# ppc_sys.net
KiCad netlist of a schematic drawn in Altium Designer
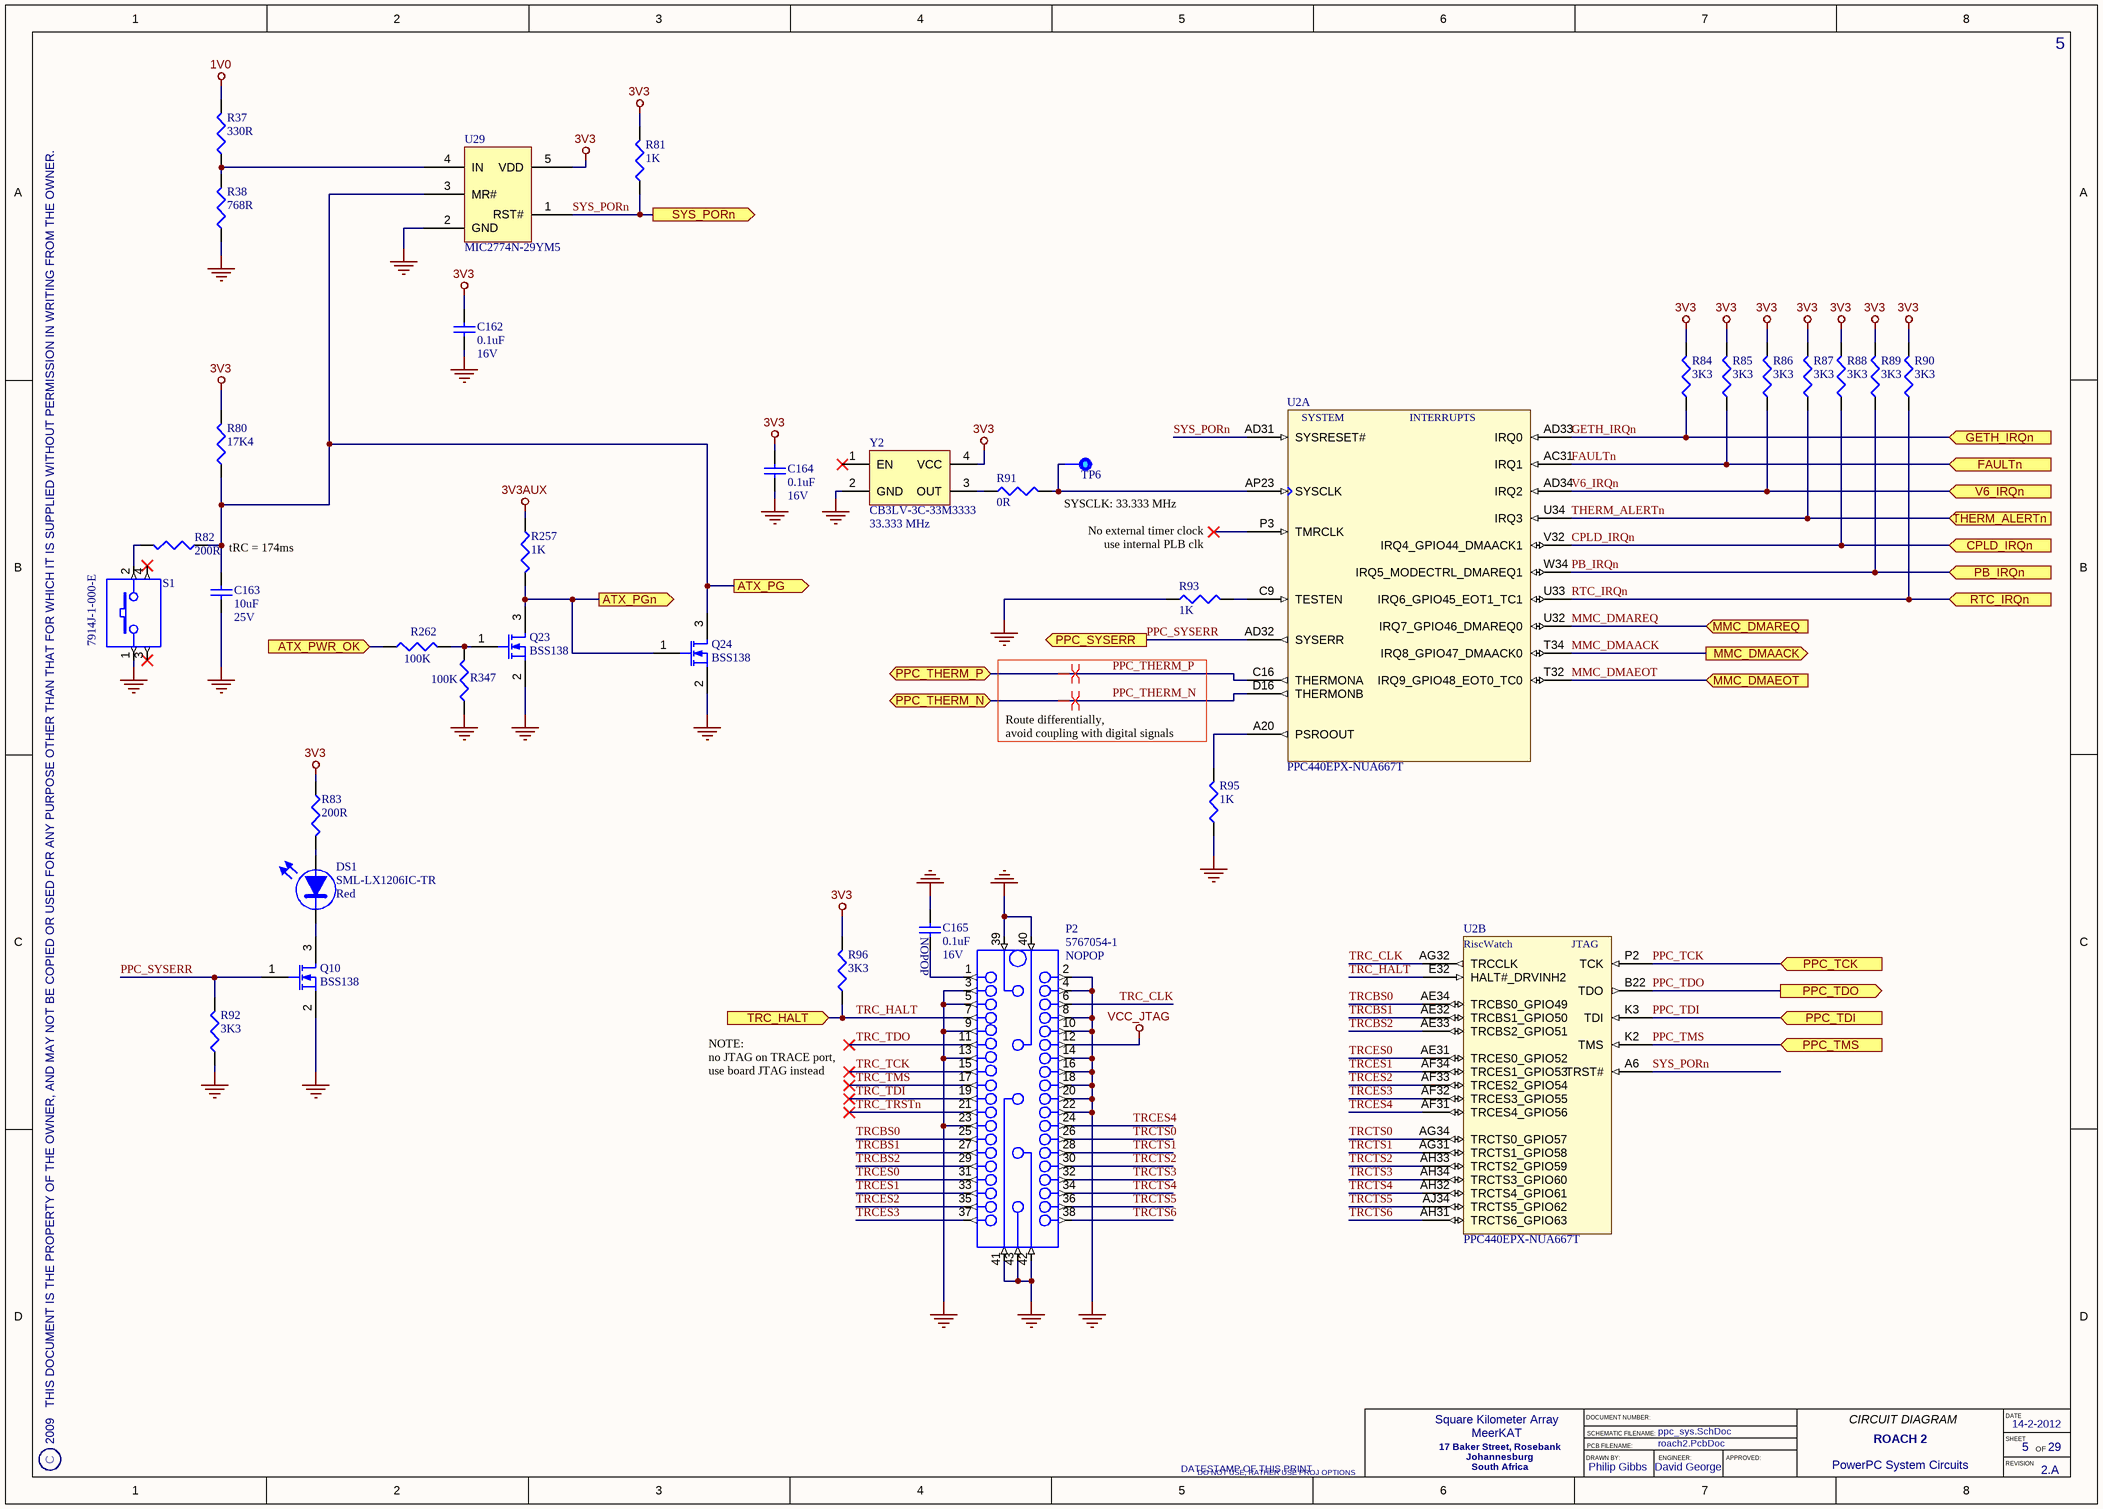
[diagram p0: ppc_sys.SchDoc]

(export (version "E")
  (design (tool "Eeschema 10.0.6"))
  (components
    (comp (ref "C162")
      (value "0.1uF")
      (footprint "CAPC1005X60L")
      (description "0.1uF, Ceramic Capacitor")
      (fields
        (field (name "RATING") "16V")
        (field (name "MANUFACTURER") "VENKEL")
        (field (name "PARTNUM") "C0402X7R160-104KN")
      )
      (libsource (lib "altium_db") (part "CapStd"))
    )
    (comp (ref "C163")
      (value "10uF")
      (footprint "CAPC3225X200L")
      (description "10uF, Ceramic Capacitor")
      (fields
        (field (name "RATING") "25V")
        (field (name "MANUFACTURER") "MURATA")
        (field (name "PARTNUM") "GRM32DR61E106KA12L")
      )
      (libsource (lib "altium_db") (part "CapStd"))
    )
    (comp (ref "C164")
      (value "0.1uF")
      (footprint "CAPC1005X60L")
      (description "0.1uF, Ceramic Capacitor")
      (fields
        (field (name "RATING") "16V")
        (field (name "MANUFACTURER") "VENKEL")
        (field (name "PARTNUM") "C0402X7R160-104KN")
      )
      (libsource (lib "altium_db") (part "CapStd"))
    )
    (comp (ref "C165")
      (value "0.1uF")
      (footprint "CAPC1005X60L")
      (description "0.1uF, Ceramic Capacitor")
      (fields
        (field (name "RATING") "16V")
        (field (name "MANUFACTURER") "VENKEL")
        (field (name "PARTNUM") "C0402X7R160-104KN")
      )
      (libsource (lib "altium_db") (part "CapStd"))
    )
    (comp (ref "DS1")
      (value "SML-LX1206IC-TR")
      (footprint "LEDC3216X120N")
      (description "Red, Surface mount, LED, 1206")
      (fields (field (name "MANUFACTURER") "LUMEX") (field (name "COLOUR") "Red"))
      (libsource (lib "altium_db") (part "LEDSTD"))
    )
    (comp (ref "P2")
      (value "5767054-1")
      (footprint "TYCO_5767054-1")
      (description "TRACE Debug Interface Receptacle")
      (fields (field (name "PARTNUM") "5767054-1") (field (name "MANUFACTURER") "TYCO"))
      (libsource (lib "altium_db") (part "5767054"))
    )
    (comp (ref "Q10")
      (value "BSS138")
      (footprint "SOT95P245X110-3N")
      (description "N-Channel Logic Level Enhancement Mode Field Effect Transistor")
      (fields (field (name "MANUFACTURER") "Fairchild Semiconductor"))
      (libsource (lib "altium_db") (part "BSS138"))
    )
    (comp (ref "Q23")
      (value "BSS138")
      (footprint "SOT95P245X110-3N")
      (description "N-Channel Logic Level Enhancement Mode Field Effect Transistor")
      (fields (field (name "MANUFACTURER") "Fairchild Semiconductor"))
      (libsource (lib "altium_db") (part "BSS138"))
    )
    (comp (ref "Q24")
      (value "BSS138")
      (footprint "SOT95P245X110-3N")
      (description "N-Channel Logic Level Enhancement Mode Field Effect Transistor")
      (fields (field (name "MANUFACTURER") "Fairchild Semiconductor"))
      (libsource (lib "altium_db") (part "BSS138"))
    )
    (comp (ref "R37")
      (value "330R")
      (footprint "RESC1005X40L")
      (description "330R, 1.1mm x 0.5mm, Thick Film Resistor")
      (fields (field (name "MANUFACTURER") "ROYALOHM") (field (name "PARTNUM") "0402WGF0331T1E"))
      (libsource (lib "Altium_DB") (part "ResStd"))
    )
    (comp (ref "R38")
      (value "768R")
      (footprint "RESC1005X40L")
      (description "768R, 1.1mm x 0.5mm, Thick Film Resistor")
      (fields (field (name "MANUFACTURER") "ROYALOHM") (field (name "PARTNUM") "0402WGF7680T1E"))
      (libsource (lib "Altium_DB") (part "ResStd"))
    )
    (comp (ref "R80")
      (value "17K4")
      (footprint "RESC1005X40L")
      (description "17K4, 1.1mm x 0.5mm, Thick Film Resistor")
      (fields (field (name "Comment") "ResStd"))
      (libsource (lib "altium_db") (part "ResStd"))
    )
    (comp (ref "R81")
      (value "1K")
      (footprint "RESC1005X40L")
      (description "1K, 1.1mm x 0.5mm, Thick Film Resistor")
      (fields (field (name "MANUFACTURER") "ROYALOHM") (field (name "PARTNUM") "0402WGJ0102T1E"))
      (libsource (lib "Altium_DB") (part "ResStd"))
    )
    (comp (ref "R82")
      (value "200R")
      (footprint "RESC1005X40L")
      (description "200R, 1.1mm x 0.5mm, Thick Film Resistor")
      (fields (field (name "MANUFACTURER") "ROYALOHM") (field (name "PARTNUM") "0402WGF0201T1E"))
      (libsource (lib "altium_db") (part "ResStd"))
    )
    (comp (ref "R83")
      (value "200R")
      (footprint "RESC1005X40L")
      (description "200R, 1.1mm x 0.5mm, Thick Film Resistor")
      (fields (field (name "MANUFACTURER") "ROYALOHM") (field (name "PARTNUM") "0402WGF0201T1E"))
      (libsource (lib "altium_db") (part "ResStd"))
    )
    (comp (ref "R84")
      (value "3K3")
      (footprint "RESC1005X40L")
      (description "3K3, 1.1mm x 0.5mm, Thick Film Resistor")
      (fields (field (name "MANUFACTURER") "ROYALOHM") (field (name "PARTNUM") "0402WGJ0332T1E"))
      (libsource (lib "altium_db") (part "ResStd"))
    )
    (comp (ref "R85")
      (value "3K3")
      (footprint "RESC1005X40L")
      (description "3K3, 1.1mm x 0.5mm, Thick Film Resistor")
      (fields (field (name "MANUFACTURER") "ROYALOHM") (field (name "PARTNUM") "0402WGJ0332T1E"))
      (libsource (lib "altium_db") (part "ResStd"))
    )
    (comp (ref "R86")
      (value "3K3")
      (footprint "RESC1005X40L")
      (description "3K3, 1.1mm x 0.5mm, Thick Film Resistor")
      (fields (field (name "MANUFACTURER") "ROYALOHM") (field (name "PARTNUM") "0402WGJ0332T1E"))
      (libsource (lib "altium_db") (part "ResStd"))
    )
    (comp (ref "R87")
      (value "3K3")
      (footprint "RESC1005X40L")
      (description "3K3, 1.1mm x 0.5mm, Thick Film Resistor")
      (fields (field (name "MANUFACTURER") "ROYALOHM") (field (name "PARTNUM") "0402WGJ0332T1E"))
      (libsource (lib "altium_db") (part "ResStd"))
    )
    (comp (ref "R88")
      (value "3K3")
      (footprint "RESC1005X40L")
      (description "3K3, 1.1mm x 0.5mm, Thick Film Resistor")
      (fields (field (name "MANUFACTURER") "ROYALOHM") (field (name "PARTNUM") "0402WGJ0332T1E"))
      (libsource (lib "altium_db") (part "ResStd"))
    )
    (comp (ref "R89")
      (value "3K3")
      (footprint "RESC1005X40L")
      (description "3K3, 1.1mm x 0.5mm, Thick Film Resistor")
      (fields (field (name "MANUFACTURER") "ROYALOHM") (field (name "PARTNUM") "0402WGJ0332T1E"))
      (libsource (lib "altium_db") (part "ResStd"))
    )
    (comp (ref "R90")
      (value "3K3")
      (footprint "RESC1005X40L")
      (description "3K3, 1.1mm x 0.5mm, Thick Film Resistor")
      (fields (field (name "MANUFACTURER") "ROYALOHM") (field (name "PARTNUM") "0402WGJ0332T1E"))
      (libsource (lib "altium_db") (part "ResStd"))
    )
    (comp (ref "R91")
      (value "0R")
      (footprint "RESC1005X40L")
      (description "0R, 1.1mm x 0.5mm, Thick Film Resistor")
      (fields (field (name "MANUFACTURER") "ROYALOHM") (field (name "PARTNUM") "0402WG00000T1E"))
      (libsource (lib "altium_db") (part "ResStd"))
    )
    (comp (ref "R92")
      (value "3K3")
      (footprint "RESC1005X40L")
      (description "3K3, 1.1mm x 0.5mm, Thick Film Resistor")
      (fields (field (name "MANUFACTURER") "ROYALOHM") (field (name "PARTNUM") "0402WGJ0332T1E"))
      (libsource (lib "altium_db") (part "ResStd"))
    )
    (comp (ref "R93")
      (value "1K")
      (footprint "RESC1005X40L")
      (description "1K, 1.1mm x 0.5mm, Thick Film Resistor")
      (fields (field (name "MANUFACTURER") "ROYALOHM") (field (name "PARTNUM") "0402WGJ0102T1E"))
      (libsource (lib "altium_db") (part "ResStd"))
    )
    (comp (ref "R95")
      (value "1K")
      (footprint "RESC1005X40L")
      (description "1K, 1.1mm x 0.5mm, Thick Film Resistor")
      (fields (field (name "MANUFACTURER") "ROYALOHM") (field (name "PARTNUM") "0402WGJ0102T1E"))
      (libsource (lib "altium_db") (part "ResStd"))
    )
    (comp (ref "R96")
      (value "3K3")
      (footprint "RESC1005X40L")
      (description "3K3, 1.1mm x 0.5mm, Thick Film Resistor")
      (fields (field (name "MANUFACTURER") "ROYALOHM") (field (name "PARTNUM") "0402WGJ0332T1E"))
      (libsource (lib "altium_db") (part "ResStd"))
    )
    (comp (ref "R257")
      (value "1K")
      (footprint "RESC1005X40L")
      (description "1K, 1.1mm x 0.5mm, Thick Film Resistor")
      (fields (field (name "MANUFACTURER") "ROYALOHM") (field (name "PARTNUM") "0402WGJ0102T1E"))
      (libsource (lib "Altium_DB") (part "ResStd"))
    )
    (comp (ref "R262")
      (value "100K")
      (footprint "RESC1005X40L")
      (description "100K, 1.1mm x 0.5mm, Thick Film Resistor")
      (fields (field (name "MANUFACTURER") "ROYALOHM") (field (name "PARTNUM") "0402WGF1003T1E"))
      (libsource (lib "Altium_DB") (part "ResStd"))
    )
    (comp (ref "R347")
      (value "100K")
      (footprint "RESC1005X40L")
      (description "100K, 1.1mm x 0.5mm, Thick Film Resistor")
      (fields (field (name "MANUFACTURER") "ROYALOHM") (field (name "PARTNUM") "0402WGF1003T1E"))
      (libsource (lib "Altium_DB") (part "ResStd"))
    )
    (comp (ref "S1")
      (value "7914J-1-000-E")
      (footprint "7914J-X-XXX-X")
      (description "4mm, Surface mount, Sealed Key Switch")
      (fields (field (name "PARTNUM") "7914J-1-000-E") (field (name "MANUFACTURER") "BOURNS"))
      (libsource (lib "altium_db") (part "7914X-X-XXX-X"))
    )
    (comp (ref "TP6")
      (value "Testpoint")
      (footprint "TP100")
      (description "1mm Diameter, through-hole, Circular Test-point")
      (libsource (lib "altium_db") (part "Testpoint"))
    )
    (comp (ref "U2")
      (value "PPC440EPX-NUA667T")
      (footprint "TE-PBGA680")
      (description "667MHz, non-RoHS, PPC440EPx uProcessor")
      (fields (field (name "MANUFACTURER") "Applied Micro"))
      (libsource (lib "altium_db") (part "PPC440EPX"))
    )
    (comp (ref "U29")
      (value "MIC2774N-29YM5")
      (footprint "SOT23-5")
      (description "Dual-power low voltage supervisor")
      (fields (field (name "MANUFACTURER") "Micrel"))
      (libsource (lib "altium_db") (part "MIC2774N-29"))
    )
    (comp (ref "Y2")
      (value "CB3LV-3C-33M3333")
      (footprint "CB3X-X-XMX")
      (description "Surface mount, 33.3333 MHz, 3V3 Clock, oscillator")
      (fields
        (field (name "PARTNUM") "CB3LV-3C-33M3333")
        (field (name "FREQUENCY") "33.333 MHz")
        (field (name "MANUFACTURER") "CTS")
      )
      (libsource (lib "altium_db") (part "CB3LV-3C-33M3333"))
    )
  )
  (nets
    (net (code "1") (name "/ATX_PG") (class "Default")
      (node (ref "C163") (pin "2") (pinfunction "2_2") (pintype "passive"))
      (node (ref "Q24") (pin "3") (pinfunction "D_3") (pintype "passive"))
      (node (ref "R80") (pin "1") (pinfunction "1_1") (pintype "passive"))
      (node (ref "R82") (pin "1") (pinfunction "1_1") (pintype "passive"))
      (node (ref "U29") (pin "3") (pinfunction "MR#_3") (pintype "passive"))
    )
    (net (code "2") (name "/ATX_PGn") (class "Default")
      (node (ref "Q23") (pin "3") (pinfunction "D_3") (pintype "passive"))
      (node (ref "Q24") (pin "1") (pinfunction "G_1") (pintype "passive"))
      (node (ref "R257") (pin "2") (pinfunction "2_2") (pintype "passive"))
    )
    (net (code "3") (name "/ATX_PWR_OK") (class "Default")
      (node (ref "R262") (pin "1") (pinfunction "1_1") (pintype "passive"))
    )
    (net (code "4") (name "/CPLD_IRQn") (class "Default")
      (node (ref "R88") (pin "1") (pinfunction "1_1") (pintype "passive"))
      (node (ref "U2") (pin "V32") (pinfunction "IRQ4_GPIO44_DMAACK1_V32") (pintype "bidirectional"))
    )
    (net (code "5") (name "/FAULTn") (class "Default")
      (node (ref "R85") (pin "1") (pinfunction "1_1") (pintype "passive"))
      (node (ref "U2") (pin "AC31") (pinfunction "IRQ1_AC31") (pintype "input"))
    )
    (net (code "6") (name "/GETH_IRQn") (class "Default")
      (node (ref "R84") (pin "1") (pinfunction "1_1") (pintype "passive"))
      (node (ref "U2") (pin "AD33") (pinfunction "IRQ0_AD33") (pintype "input"))
    )
    (net (code "7") (name "/MMC_DMAACK") (class "Default")
      (node (ref "U2") (pin "T34") (pinfunction "IRQ8_GPIO47_DMAACK0_T34") (pintype "bidirectional"))
    )
    (net (code "8") (name "/MMC_DMAEOT") (class "Default")
      (node (ref "U2") (pin "T32") (pinfunction "IRQ9_GPIO48_EOT0_TC0_T32") (pintype "bidirectional"))
    )
    (net (code "9") (name "/MMC_DMAREQ") (class "Default")
      (node (ref "U2") (pin "U32") (pinfunction "IRQ7_GPIO46_DMAREQ0_U32") (pintype "bidirectional"))
    )
    (net (code "10") (name "/PB_IRQn") (class "Default")
      (node (ref "R89") (pin "1") (pinfunction "1_1") (pintype "passive"))
      (node (ref "U2") (pin "W34") (pinfunction "IRQ5_MODECTRL_DMAREQ1_W34") (pintype "bidirectional"))
    )
    (net (code "11") (name "/PPC_SYSERR") (class "Default")
      (node (ref "Q10") (pin "1") (pinfunction "G_1") (pintype "passive"))
      (node (ref "R92") (pin "2") (pinfunction "2_2") (pintype "passive"))
      (node (ref "U2") (pin "AD32") (pinfunction "SYSERR_AD32") (pintype "output"))
    )
    (net (code "12") (name "/PPC_TCK") (class "Default")
      (node (ref "U2") (pin "P2") (pinfunction "TCK_P2") (pintype "input"))
    )
    (net (code "13") (name "/PPC_TDI") (class "Default")
      (node (ref "U2") (pin "K3") (pinfunction "TDI_K3") (pintype "input"))
    )
    (net (code "14") (name "/PPC_TDO") (class "Default")
      (node (ref "U2") (pin "B22") (pinfunction "TDO_B22") (pintype "output"))
    )
    (net (code "15") (name "/PPC_THERM_N") (class "Default")
      (node (ref "U2") (pin "D16") (pinfunction "THERMONB_D16") (pintype "output"))
    )
    (net (code "16") (name "/PPC_THERM_P") (class "Default")
      (node (ref "U2") (pin "C16") (pinfunction "THERMONA_C16") (pintype "output"))
    )
    (net (code "17") (name "/PPC_TMS") (class "Default")
      (node (ref "U2") (pin "K2") (pinfunction "TMS_K2") (pintype "input"))
    )
    (net (code "18") (name "/RTC_IRQn") (class "Default")
      (node (ref "R90") (pin "1") (pinfunction "1_1") (pintype "passive"))
      (node (ref "U2") (pin "U33") (pinfunction "IRQ6_GPIO45_EOT1_TC1_U33") (pintype "bidirectional"))
    )
    (net (code "19") (name "/SYS_PORn") (class "Default")
      (node (ref "R81") (pin "1") (pinfunction "1_1") (pintype "passive"))
      (node (ref "U2") (pin "A6") (pinfunction "TRST#_A6") (pintype "input"))
      (node (ref "U2") (pin "AD31") (pinfunction "SYSRESET#_AD31") (pintype "input"))
      (node (ref "U29") (pin "1") (pinfunction "RST#_1") (pintype "passive"))
    )
    (net (code "20") (name "/THERM_ALERTn") (class "Default")
      (node (ref "R87") (pin "1") (pinfunction "1_1") (pintype "passive"))
      (node (ref "U2") (pin "U34") (pinfunction "IRQ3_U34") (pintype "input"))
    )
    (net (code "21") (name "/TRCBS0") (class "Default")
      (node (ref "P2") (pin "25") (pinfunction "25_25") (pintype "output"))
      (node (ref "U2") (pin "AE34") (pinfunction "TRCBS0_GPIO49_AE34") (pintype "bidirectional"))
    )
    (net (code "22") (name "/TRCBS1") (class "Default")
      (node (ref "P2") (pin "27") (pinfunction "27_27") (pintype "output"))
      (node (ref "U2") (pin "AE32") (pinfunction "TRCBS1_GPIO50_AE32") (pintype "bidirectional"))
    )
    (net (code "23") (name "/TRCBS2") (class "Default")
      (node (ref "P2") (pin "29") (pinfunction "29_29") (pintype "output"))
      (node (ref "U2") (pin "AE33") (pinfunction "TRCBS2_GPIO51_AE33") (pintype "bidirectional"))
    )
    (net (code "24") (name "/TRCES0") (class "Default")
      (node (ref "P2") (pin "31") (pinfunction "31_31") (pintype "output"))
      (node (ref "U2") (pin "AE31") (pinfunction "TRCES0_GPIO52_AE31") (pintype "bidirectional"))
    )
    (net (code "25") (name "/TRCES1") (class "Default")
      (node (ref "P2") (pin "33") (pinfunction "33_33") (pintype "output"))
      (node (ref "U2") (pin "AF34") (pinfunction "TRCES1_GPIO53_AF34") (pintype "bidirectional"))
    )
    (net (code "26") (name "/TRCES2") (class "Default")
      (node (ref "P2") (pin "35") (pinfunction "35_35") (pintype "output"))
      (node (ref "U2") (pin "AF33") (pinfunction "TRCES2_GPIO54_AF33") (pintype "bidirectional"))
    )
    (net (code "27") (name "/TRCES3") (class "Default")
      (node (ref "P2") (pin "37") (pinfunction "37_37") (pintype "output"))
      (node (ref "U2") (pin "AF32") (pinfunction "TRCES3_GPIO55_AF32") (pintype "bidirectional"))
    )
    (net (code "28") (name "/TRCES4") (class "Default")
      (node (ref "P2") (pin "24") (pinfunction "24_24") (pintype "output"))
      (node (ref "U2") (pin "AF31") (pinfunction "TRCES4_GPIO56_AF31") (pintype "bidirectional"))
    )
    (net (code "29") (name "/TRCTS0") (class "Default")
      (node (ref "P2") (pin "26") (pinfunction "26_26") (pintype "output"))
      (node (ref "U2") (pin "AG34") (pinfunction "TRCTS0_GPIO57_AG34") (pintype "bidirectional"))
    )
    (net (code "30") (name "/TRCTS1") (class "Default")
      (node (ref "P2") (pin "28") (pinfunction "28_28") (pintype "output"))
      (node (ref "U2") (pin "AG31") (pinfunction "TRCTS1_GPIO58_AG31") (pintype "bidirectional"))
    )
    (net (code "31") (name "/TRCTS2") (class "Default")
      (node (ref "P2") (pin "30") (pinfunction "30_30") (pintype "output"))
      (node (ref "U2") (pin "AH33") (pinfunction "TRCTS2_GPIO59_AH33") (pintype "bidirectional"))
    )
    (net (code "32") (name "/TRCTS3") (class "Default")
      (node (ref "P2") (pin "32") (pinfunction "32_32") (pintype "output"))
      (node (ref "U2") (pin "AH34") (pinfunction "TRCTS3_GPIO60_AH34") (pintype "bidirectional"))
    )
    (net (code "33") (name "/TRCTS4") (class "Default")
      (node (ref "P2") (pin "34") (pinfunction "34_34") (pintype "output"))
      (node (ref "U2") (pin "AH32") (pinfunction "TRCTS4_GPIO61_AH32") (pintype "bidirectional"))
    )
    (net (code "34") (name "/TRCTS5") (class "Default")
      (node (ref "P2") (pin "36") (pinfunction "36_36") (pintype "output"))
      (node (ref "U2") (pin "AJ34") (pinfunction "TRCTS5_GPIO62_AJ34") (pintype "bidirectional"))
    )
    (net (code "35") (name "/TRCTS6") (class "Default")
      (node (ref "P2") (pin "38") (pinfunction "38_38") (pintype "output"))
      (node (ref "U2") (pin "AH31") (pinfunction "TRCTS6_GPIO63_AH31") (pintype "bidirectional"))
    )
    (net (code "36") (name "/TRC_CLK") (class "Default")
      (node (ref "P2") (pin "6") (pinfunction "6_6") (pintype "output"))
      (node (ref "U2") (pin "AG32") (pinfunction "TRCCLK_AG32") (pintype "output"))
    )
    (net (code "37") (name "/TRC_HALT") (class "Default")
      (node (ref "P2") (pin "7") (pinfunction "7_7") (pintype "output"))
      (node (ref "R96") (pin "1") (pinfunction "1_1") (pintype "passive"))
      (node (ref "U2") (pin "E32") (pinfunction "HALT#_DRVINH2_E32") (pintype "input"))
    )
    (net (code "38") (name "/TRC_TCK") (class "Default")
      (node (ref "P2") (pin "15") (pinfunction "15_15") (pintype "output+no_connect"))
    )
    (net (code "39") (name "/TRC_TDI") (class "Default")
      (node (ref "P2") (pin "19") (pinfunction "19_19") (pintype "output+no_connect"))
    )
    (net (code "40") (name "/TRC_TDO") (class "Default")
      (node (ref "P2") (pin "11") (pinfunction "11_11") (pintype "output+no_connect"))
    )
    (net (code "41") (name "/TRC_TMS") (class "Default")
      (node (ref "P2") (pin "17") (pinfunction "17_17") (pintype "output+no_connect"))
    )
    (net (code "42") (name "/TRC_TRSTn") (class "Default")
      (node (ref "P2") (pin "21") (pinfunction "21_21") (pintype "output+no_connect"))
    )
    (net (code "43") (name "/V6_IRQn") (class "Default")
      (node (ref "R86") (pin "1") (pinfunction "1_1") (pintype "passive"))
      (node (ref "U2") (pin "AD34") (pinfunction "IRQ2_AD34") (pintype "input"))
    )
    (net (code "44") (name "1V0") (class "Default")
      (node (ref "R37") (pin "2") (pinfunction "2_2") (pintype "passive"))
    )
    (net (code "45") (name "3V3") (class "Default")
      (node (ref "C162") (pin "2") (pinfunction "2_2") (pintype "passive"))
      (node (ref "C164") (pin "2") (pinfunction "2_2") (pintype "passive"))
      (node (ref "R80") (pin "2") (pinfunction "2_2") (pintype "passive"))
      (node (ref "R81") (pin "2") (pinfunction "2_2") (pintype "passive"))
      (node (ref "R83") (pin "1") (pinfunction "1_1") (pintype "passive"))
      (node (ref "R84") (pin "2") (pinfunction "2_2") (pintype "passive"))
      (node (ref "R85") (pin "2") (pinfunction "2_2") (pintype "passive"))
      (node (ref "R86") (pin "2") (pinfunction "2_2") (pintype "passive"))
      (node (ref "R87") (pin "2") (pinfunction "2_2") (pintype "passive"))
      (node (ref "R88") (pin "2") (pinfunction "2_2") (pintype "passive"))
      (node (ref "R89") (pin "2") (pinfunction "2_2") (pintype "passive"))
      (node (ref "R90") (pin "2") (pinfunction "2_2") (pintype "passive"))
      (node (ref "R96") (pin "2") (pinfunction "2_2") (pintype "passive"))
      (node (ref "U29") (pin "5") (pinfunction "VDD_5") (pintype "passive"))
      (node (ref "Y2") (pin "4") (pinfunction "VCC_4") (pintype "passive"))
    )
    (net (code "46") (name "3V3AUX") (class "Default")
      (node (ref "R257") (pin "1") (pinfunction "1_1") (pintype "passive"))
    )
    (net (code "47") (name "GND") (class "Default")
      (node (ref "C162") (pin "1") (pinfunction "1_1") (pintype "passive"))
      (node (ref "C163") (pin "1") (pinfunction "1_1") (pintype "passive"))
      (node (ref "C164") (pin "1") (pinfunction "1_1") (pintype "passive"))
      (node (ref "C165") (pin "2") (pinfunction "2_2") (pintype "passive"))
      (node (ref "P2") (pin "10") (pinfunction "10_10") (pintype "output"))
      (node (ref "P2") (pin "13") (pinfunction "13_13") (pintype "output"))
      (node (ref "P2") (pin "14") (pinfunction "14_14") (pintype "output"))
      (node (ref "P2") (pin "16") (pinfunction "16_16") (pintype "output"))
      (node (ref "P2") (pin "18") (pinfunction "18_18") (pintype "output"))
      (node (ref "P2") (pin "2") (pinfunction "2_2") (pintype "output"))
      (node (ref "P2") (pin "20") (pinfunction "20_20") (pintype "output"))
      (node (ref "P2") (pin "22") (pinfunction "22_22") (pintype "output"))
      (node (ref "P2") (pin "23") (pinfunction "23_23") (pintype "output"))
      (node (ref "P2") (pin "3") (pinfunction "3_3") (pintype "output"))
      (node (ref "P2") (pin "39") (pinfunction "39_39") (pintype "input"))
      (node (ref "P2") (pin "4") (pinfunction "4_4") (pintype "output"))
      (node (ref "P2") (pin "40") (pinfunction "40_40") (pintype "input"))
      (node (ref "P2") (pin "41") (pinfunction "41_41") (pintype "input"))
      (node (ref "P2") (pin "42") (pinfunction "42_42") (pintype "input"))
      (node (ref "P2") (pin "43") (pinfunction "43_43") (pintype "input"))
      (node (ref "P2") (pin "5") (pinfunction "5_5") (pintype "output"))
      (node (ref "P2") (pin "8") (pinfunction "8_8") (pintype "output"))
      (node (ref "P2") (pin "9") (pinfunction "9_9") (pintype "output"))
      (node (ref "Q10") (pin "2") (pinfunction "S_2") (pintype "passive"))
      (node (ref "Q23") (pin "2") (pinfunction "S_2") (pintype "passive"))
      (node (ref "Q24") (pin "2") (pinfunction "S_2") (pintype "passive"))
      (node (ref "R347") (pin "1") (pinfunction "1_1") (pintype "passive"))
      (node (ref "R38") (pin "1") (pinfunction "1_1") (pintype "passive"))
      (node (ref "R92") (pin "1") (pinfunction "1_1") (pintype "passive"))
      (node (ref "R93") (pin "1") (pinfunction "1_1") (pintype "passive"))
      (node (ref "R95") (pin "1") (pinfunction "1_1") (pintype "passive"))
      (node (ref "S1") (pin "1") (pinfunction "1_1") (pintype "output"))
      (node (ref "U29") (pin "2") (pinfunction "GND_2") (pintype "passive"))
      (node (ref "Y2") (pin "2") (pinfunction "GND_2") (pintype "passive"))
    )
    (net (code "48") (name "Net-(C165-Pad1)") (class "Default")
      (node (ref "C165") (pin "1") (pinfunction "1_1") (pintype "passive"))
      (node (ref "P2") (pin "1") (pinfunction "1_1") (pintype "output"))
    )
    (net (code "49") (name "Net-(DS1-A)") (class "Default")
      (node (ref "DS1") (pin "2") (pinfunction "A_2") (pintype "passive"))
      (node (ref "R83") (pin "2") (pinfunction "2_2") (pintype "passive"))
    )
    (net (code "50") (name "Net-(DS1-K)") (class "Default")
      (node (ref "DS1") (pin "1") (pinfunction "K_1") (pintype "passive"))
      (node (ref "Q10") (pin "3") (pinfunction "D_3") (pintype "passive"))
    )
    (net (code "51") (name "Net-(Q23-G)") (class "Default")
      (node (ref "Q23") (pin "1") (pinfunction "G_1") (pintype "passive"))
      (node (ref "R262") (pin "2") (pinfunction "2_2") (pintype "passive"))
      (node (ref "R347") (pin "2") (pinfunction "2_2") (pintype "passive"))
    )
    (net (code "52") (name "Net-(R82-Pad2)") (class "Default")
      (node (ref "R82") (pin "2") (pinfunction "2_2") (pintype "passive"))
      (node (ref "S1") (pin "2") (pinfunction "2_2") (pintype "output"))
    )
    (net (code "53") (name "Net-(U2A-PSROOUT)") (class "Default")
      (node (ref "R95") (pin "2") (pinfunction "2_2") (pintype "passive"))
      (node (ref "U2") (pin "A20") (pinfunction "PSROOUT_A20") (pintype "output"))
    )
    (net (code "54") (name "Net-(U2A-SYSCLK)") (class "Default")
      (node (ref "R91") (pin "2") (pinfunction "2_2") (pintype "passive"))
      (node (ref "TP6") (pin "1") (pinfunction "1_1") (pintype "passive"))
      (node (ref "U2") (pin "AP23") (pinfunction "SYSCLK_AP23") (pintype "input"))
    )
    (net (code "55") (name "Net-(U2A-TESTEN)") (class "Default")
      (node (ref "R93") (pin "2") (pinfunction "2_2") (pintype "passive"))
      (node (ref "U2") (pin "C9") (pinfunction "TESTEN_C9") (pintype "input"))
    )
    (net (code "56") (name "Net-(U29-IN)") (class "Default")
      (node (ref "R37") (pin "1") (pinfunction "1_1") (pintype "passive"))
      (node (ref "R38") (pin "2") (pinfunction "2_2") (pintype "passive"))
      (node (ref "U29") (pin "4") (pinfunction "IN_4") (pintype "passive"))
    )
    (net (code "57") (name "Net-(Y2-OUT)") (class "Default")
      (node (ref "R91") (pin "1") (pinfunction "1_1") (pintype "passive"))
      (node (ref "Y2") (pin "3") (pinfunction "OUT_3") (pintype "passive"))
    )
    (net (code "58") (name "VCC_JTAG") (class "Default")
      (node (ref "P2") (pin "12") (pinfunction "12_12") (pintype "output"))
    )
    (net (code "59") (name "unconnected-(S1-Pad3)") (class "Default")
      (node (ref "S1") (pin "3") (pinfunction "3_3") (pintype "output+no_connect"))
    )
    (net (code "60") (name "unconnected-(S1-Pad4)") (class "Default")
      (node (ref "S1") (pin "4") (pinfunction "4_4") (pintype "output+no_connect"))
    )
    (net (code "61") (name "unconnected-(U2A-TMRCLK-PadP3)") (class "Default")
      (node (ref "U2") (pin "P3") (pinfunction "TMRCLK_P3") (pintype "input+no_connect"))
    )
    (net (code "62") (name "unconnected-(Y2-EN-Pad1)") (class "Default")
      (node (ref "Y2") (pin "1") (pinfunction "EN_1") (pintype "passive+no_connect"))
    )
  )
)
